# mainboard.net
KiCad netlist of a schematic drawn in EAGLE
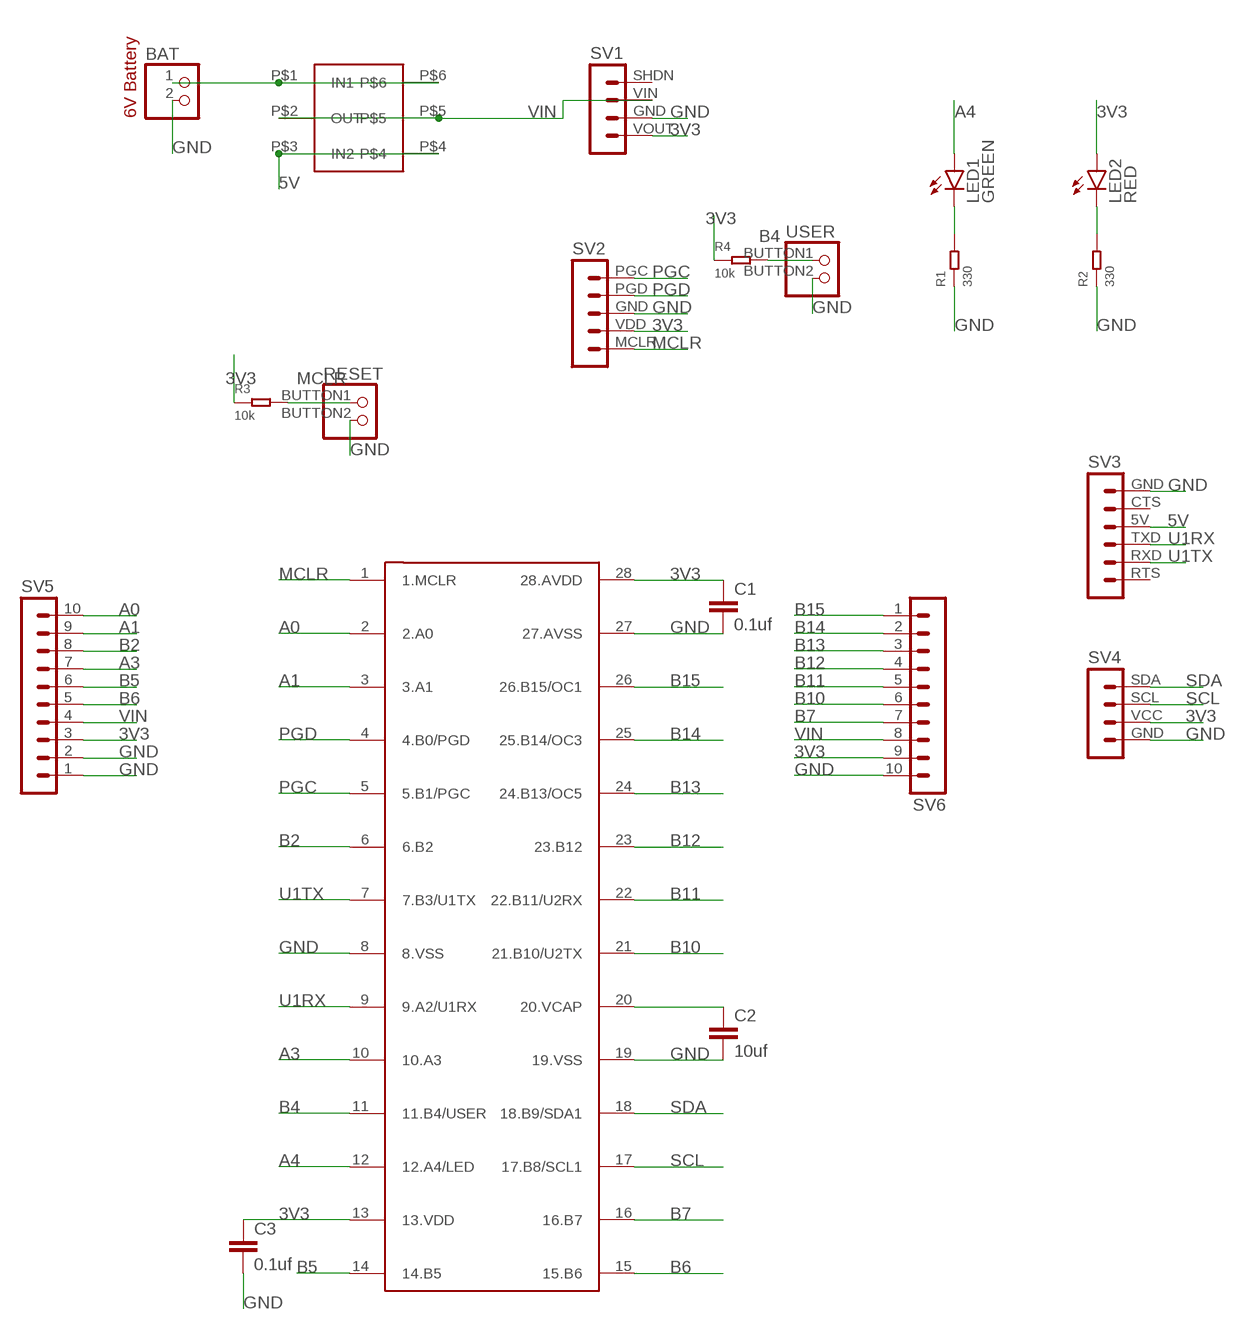
[diagram p0: schematic, sheet 1]

(export (version "E")
  (design (tool "Eeschema 10.0.6"))
  (components
    (comp (ref "BAT")
      (value "PINHD-1X2")
      (footprint "eagle-import:1X02")
      (libsource (lib "eagle-import") (part "PINHD-1X2"))
    )
    (comp (ref "C1")
      (value "0.1uf")
      (footprint "eagle-import:C2.5-3")
      (libsource (lib "eagle-import") (part "C2,5-3"))
    )
    (comp (ref "C2")
      (value "10uf")
      (footprint "eagle-import:C2.5-3")
      (libsource (lib "eagle-import") (part "C2,5-3"))
    )
    (comp (ref "C3")
      (value "0.1uf")
      (footprint "eagle-import:C2.5-3")
      (libsource (lib "eagle-import") (part "C2,5-3"))
    )
    (comp (ref "LED1")
      (value "GREEN")
      (footprint "eagle-import:LED3MM")
      (libsource (lib "eagle-import") (part "LED3MM"))
    )
    (comp (ref "LED2")
      (value "RED")
      (footprint "eagle-import:LED3MM")
      (libsource (lib "eagle-import") (part "LED3MM"))
    )
    (comp (ref "R1")
      (value "330")
      (footprint "eagle-import:PR-D2.3XL6.5MM")
      (fields (field (name "MPN") "FHCFR-1/4W-334J"))
      (libsource (lib "eagle-import") (part "DIP-RES-1/4W(PR-D2.3XL6.5MM)"))
    )
    (comp (ref "R2")
      (value "330")
      (footprint "eagle-import:PR-D2.3XL6.5MM")
      (fields (field (name "MPN") "FHCFR-1/4W-334J"))
      (libsource (lib "eagle-import") (part "DIP-RES-1/4W(PR-D2.3XL6.5MM)"))
    )
    (comp (ref "R3")
      (value "10k")
      (footprint "eagle-import:PR-D2.3XL6.5MM")
      (fields (field (name "MPN") "FHCFR-1/4W-334J"))
      (libsource (lib "eagle-import") (part "DIP-RES-1/4W(PR-D2.3XL6.5MM)"))
    )
    (comp (ref "R4")
      (value "10k")
      (footprint "eagle-import:PR-D2.3XL6.5MM")
      (fields (field (name "MPN") "FHCFR-1/4W-334J"))
      (libsource (lib "eagle-import") (part "DIP-RES-1/4W(PR-D2.3XL6.5MM)"))
    )
    (comp (ref "RESET")
      (value "PUSHBUTTON")
      (footprint "eagle-import:PUSHBUTTON")
      (libsource (lib "eagle-import") (part "PUSHBUTTON"))
    )
    (comp (ref "SV1")
      (value "POLOLU3.3POLOLU3.3")
      (footprint "eagle-import:POLOLU3.3")
      (libsource (lib "eagle-import") (part "POLOLU3.3POLOLU3.3"))
    )
    (comp (ref "SV2")
      (value "MPLAB-SNAP")
      (footprint "eagle-import:MPLAB-SNAP")
      (libsource (lib "eagle-import") (part "MPLAB-SNAP"))
    )
    (comp (ref "SV3")
      (value "CP2104FRIEND")
      (footprint "eagle-import:CP2104FRIEND")
      (libsource (lib "eagle-import") (part "CP2104FRIEND"))
    )
    (comp (ref "SV4")
      (value "SSD1306")
      (footprint "eagle-import:SSD1306")
      (libsource (lib "eagle-import") (part "SSD1306"))
    )
    (comp (ref "SV5")
      (value "MA10-1")
      (footprint "eagle-import:MA10-1")
      (libsource (lib "eagle-import") (part "MA10-1"))
    )
    (comp (ref "SV6")
      (value "MA10-1")
      (footprint "eagle-import:MA10-1")
      (libsource (lib "eagle-import") (part "MA10-1"))
    )
    (comp (ref "U$1")
      (value "SLIDE_SWITCH")
      (footprint "eagle-import:SLIDE")
      (libsource (lib "eagle-import") (part "SLIDE_SWITCH"))
    )
    (comp (ref "U$2")
      (value "PIC32MX170F256B")
      (footprint "eagle-import:DIL28-3")
      (libsource (lib "eagle-import") (part "PIC32MX170F256B"))
    )
    (comp (ref "USER")
      (value "PUSHBUTTON")
      (footprint "eagle-import:PUSHBUTTON")
      (libsource (lib "eagle-import") (part "PUSHBUTTON"))
    )
  )
  (nets
    (net (code "1") (name "/3V3") (class "Default")
      (node (ref "C1") (pin "1") (pinfunction "1_1") (pintype "passive"))
      (node (ref "C3") (pin "1") (pinfunction "1_1") (pintype "passive"))
      (node (ref "LED2") (pin "A") (pinfunction "A_A") (pintype "passive"))
      (node (ref "R3") (pin "1") (pinfunction "1_1") (pintype "passive"))
      (node (ref "R4") (pin "1") (pinfunction "1_1") (pintype "passive"))
      (node (ref "SV1") (pin "VOUT") (pinfunction "VOUT_VOUT") (pintype "passive"))
      (node (ref "SV2") (pin "VDD") (pinfunction "VDD_VDD") (pintype "passive"))
      (node (ref "SV4") (pin "VCC") (pinfunction "VCC_VCC") (pintype "passive"))
      (node (ref "SV5") (pin "3") (pinfunction "3_3") (pintype "passive"))
      (node (ref "SV6") (pin "9") (pinfunction "9_9") (pintype "passive"))
      (node (ref "U$2") (pin "13") (pinfunction "13.VDD_13") (pintype "bidirectional"))
      (node (ref "U$2") (pin "28") (pinfunction "28.AVDD_28") (pintype "bidirectional"))
    )
    (net (code "2") (name "/5V") (class "Default")
      (node (ref "SV3") (pin "5V") (pinfunction "5V_5V") (pintype "passive"))
      (node (ref "U$1") (pin "P$3") (pinfunction "IN2_P$3") (pintype "bidirectional"))
      (node (ref "U$1") (pin "P$4") (pinfunction "P$4_P$4") (pintype "bidirectional"))
    )
    (net (code "3") (name "/A0") (class "Default")
      (node (ref "SV5") (pin "10") (pinfunction "10_10") (pintype "passive"))
      (node (ref "U$2") (pin "2") (pinfunction "2.A0_2") (pintype "bidirectional"))
    )
    (net (code "4") (name "/A1") (class "Default")
      (node (ref "SV5") (pin "9") (pinfunction "9_9") (pintype "passive"))
      (node (ref "U$2") (pin "3") (pinfunction "3.A1_3") (pintype "bidirectional"))
    )
    (net (code "5") (name "/A3") (class "Default")
      (node (ref "SV5") (pin "7") (pinfunction "7_7") (pintype "passive"))
      (node (ref "U$2") (pin "10") (pinfunction "10.A3_10") (pintype "bidirectional"))
    )
    (net (code "6") (name "/A4") (class "Default")
      (node (ref "LED1") (pin "A") (pinfunction "A_A") (pintype "passive"))
      (node (ref "U$2") (pin "12") (pinfunction "12.A4/LED_12") (pintype "bidirectional"))
    )
    (net (code "7") (name "/B2") (class "Default")
      (node (ref "SV5") (pin "8") (pinfunction "8_8") (pintype "passive"))
      (node (ref "U$2") (pin "6") (pinfunction "6.B2_6") (pintype "bidirectional"))
    )
    (net (code "8") (name "/B4") (class "Default")
      (node (ref "R4") (pin "2") (pinfunction "2_2") (pintype "passive"))
      (node (ref "U$2") (pin "11") (pinfunction "11.B4/USER_11") (pintype "bidirectional"))
      (node (ref "USER") (pin "BUTTON1") (pinfunction "1_BUTTON1") (pintype "passive"))
    )
    (net (code "9") (name "/B5") (class "Default")
      (node (ref "SV5") (pin "6") (pinfunction "6_6") (pintype "passive"))
      (node (ref "U$2") (pin "14") (pinfunction "14.B5_14") (pintype "bidirectional"))
    )
    (net (code "10") (name "/B6") (class "Default")
      (node (ref "SV5") (pin "5") (pinfunction "5_5") (pintype "passive"))
      (node (ref "U$2") (pin "15") (pinfunction "15.B6_15") (pintype "bidirectional"))
    )
    (net (code "11") (name "/B7") (class "Default")
      (node (ref "SV6") (pin "7") (pinfunction "7_7") (pintype "passive"))
      (node (ref "U$2") (pin "16") (pinfunction "16.B7_16") (pintype "bidirectional"))
    )
    (net (code "12") (name "/B10") (class "Default")
      (node (ref "SV6") (pin "6") (pinfunction "6_6") (pintype "passive"))
      (node (ref "U$2") (pin "21") (pinfunction "21.B10/U2TX_21") (pintype "bidirectional"))
    )
    (net (code "13") (name "/B11") (class "Default")
      (node (ref "SV6") (pin "5") (pinfunction "5_5") (pintype "passive"))
      (node (ref "U$2") (pin "22") (pinfunction "22.B11/U2RX_22") (pintype "bidirectional"))
    )
    (net (code "14") (name "/B12") (class "Default")
      (node (ref "SV6") (pin "4") (pinfunction "4_4") (pintype "passive"))
      (node (ref "U$2") (pin "23") (pinfunction "23.B12_23") (pintype "bidirectional"))
    )
    (net (code "15") (name "/B13") (class "Default")
      (node (ref "SV6") (pin "3") (pinfunction "3_3") (pintype "passive"))
      (node (ref "U$2") (pin "24") (pinfunction "24.B13/OC5_24") (pintype "bidirectional"))
    )
    (net (code "16") (name "/B14") (class "Default")
      (node (ref "SV6") (pin "2") (pinfunction "2_2") (pintype "passive"))
      (node (ref "U$2") (pin "25") (pinfunction "25.B14/OC3_25") (pintype "bidirectional"))
    )
    (net (code "17") (name "/B15") (class "Default")
      (node (ref "SV6") (pin "1") (pinfunction "1_1") (pintype "passive"))
      (node (ref "U$2") (pin "26") (pinfunction "26.B15/OC1_26") (pintype "bidirectional"))
    )
    (net (code "18") (name "/GND") (class "Default")
      (node (ref "BAT") (pin "2") (pinfunction "2_2") (pintype "passive"))
      (node (ref "C1") (pin "2") (pinfunction "2_2") (pintype "passive"))
      (node (ref "C2") (pin "2") (pinfunction "2_2") (pintype "passive"))
      (node (ref "C3") (pin "2") (pinfunction "2_2") (pintype "passive"))
      (node (ref "R1") (pin "1") (pinfunction "1_1") (pintype "passive"))
      (node (ref "R2") (pin "1") (pinfunction "1_1") (pintype "passive"))
      (node (ref "RESET") (pin "BUTTON2") (pinfunction "2_BUTTON2") (pintype "passive"))
      (node (ref "SV1") (pin "GND") (pinfunction "GND_GND") (pintype "passive"))
      (node (ref "SV2") (pin "GND") (pinfunction "GND_GND") (pintype "passive"))
      (node (ref "SV3") (pin "GND") (pinfunction "GND_GND") (pintype "passive"))
      (node (ref "SV4") (pin "GND") (pinfunction "GND_GND") (pintype "passive"))
      (node (ref "SV5") (pin "1") (pinfunction "1_1") (pintype "passive"))
      (node (ref "SV5") (pin "2") (pinfunction "2_2") (pintype "passive"))
      (node (ref "SV6") (pin "10") (pinfunction "10_10") (pintype "passive"))
      (node (ref "U$2") (pin "19") (pinfunction "19.VSS_19") (pintype "bidirectional"))
      (node (ref "U$2") (pin "27") (pinfunction "27.AVSS_27") (pintype "bidirectional"))
      (node (ref "U$2") (pin "8") (pinfunction "8.VSS_8") (pintype "bidirectional"))
      (node (ref "USER") (pin "BUTTON2") (pinfunction "2_BUTTON2") (pintype "passive"))
    )
    (net (code "19") (name "/MCLR") (class "Default")
      (node (ref "R3") (pin "2") (pinfunction "2_2") (pintype "passive"))
      (node (ref "RESET") (pin "BUTTON1") (pinfunction "1_BUTTON1") (pintype "passive"))
      (node (ref "SV2") (pin "MCLR") (pinfunction "MCLR_MCLR") (pintype "passive"))
      (node (ref "U$2") (pin "1") (pinfunction "1.MCLR_1") (pintype "bidirectional"))
    )
    (net (code "20") (name "/PGC") (class "Default")
      (node (ref "SV2") (pin "PGC") (pinfunction "PGC_PGC") (pintype "passive"))
      (node (ref "U$2") (pin "5") (pinfunction "5.B1/PGC_5") (pintype "bidirectional"))
    )
    (net (code "21") (name "/PGD") (class "Default")
      (node (ref "SV2") (pin "PGD") (pinfunction "PGD_PGD") (pintype "passive"))
      (node (ref "U$2") (pin "4") (pinfunction "4.B0/PGD_4") (pintype "bidirectional"))
    )
    (net (code "22") (name "/SCL") (class "Default")
      (node (ref "SV4") (pin "SCL") (pinfunction "SCL_SCL") (pintype "passive"))
      (node (ref "U$2") (pin "17") (pinfunction "17.B8/SCL1_17") (pintype "bidirectional"))
    )
    (net (code "23") (name "/SDA") (class "Default")
      (node (ref "SV4") (pin "SDA") (pinfunction "SDA_SDA") (pintype "passive"))
      (node (ref "U$2") (pin "18") (pinfunction "18.B9/SDA1_18") (pintype "bidirectional"))
    )
    (net (code "24") (name "/U1RX") (class "Default")
      (node (ref "SV3") (pin "TXD") (pinfunction "TXD_TXD") (pintype "passive"))
      (node (ref "U$2") (pin "9") (pinfunction "9.A2/U1RX_9") (pintype "bidirectional"))
    )
    (net (code "25") (name "/U1TX") (class "Default")
      (node (ref "SV3") (pin "RXD") (pinfunction "RXD_RXD") (pintype "passive"))
      (node (ref "U$2") (pin "7") (pinfunction "7.B3/U1TX_7") (pintype "bidirectional"))
    )
    (net (code "26") (name "/VIN") (class "Default")
      (node (ref "SV1") (pin "VIN") (pinfunction "VIN_VIN") (pintype "passive"))
      (node (ref "SV5") (pin "4") (pinfunction "4_4") (pintype "passive"))
      (node (ref "SV6") (pin "8") (pinfunction "8_8") (pintype "passive"))
      (node (ref "U$1") (pin "P$2") (pinfunction "OUT_P$2") (pintype "bidirectional"))
      (node (ref "U$1") (pin "P$5") (pinfunction "P$5_P$5") (pintype "bidirectional"))
    )
    (net (code "27") (name "Net-(LED1-C)") (class "Default")
      (node (ref "LED1") (pin "K") (pinfunction "C_K") (pintype "passive"))
      (node (ref "R1") (pin "2") (pinfunction "2_2") (pintype "passive"))
    )
    (net (code "28") (name "Net-(LED2-C)") (class "Default")
      (node (ref "LED2") (pin "K") (pinfunction "C_K") (pintype "passive"))
      (node (ref "R2") (pin "2") (pinfunction "2_2") (pintype "passive"))
    )
    (net (code "29") (name "Net-(U$1-IN1)") (class "Default")
      (node (ref "BAT") (pin "1") (pinfunction "1_1") (pintype "passive"))
      (node (ref "U$1") (pin "P$1") (pinfunction "IN1_P$1") (pintype "bidirectional"))
      (node (ref "U$1") (pin "P$6") (pinfunction "P$6_P$6") (pintype "bidirectional"))
    )
    (net (code "30") (name "Net-(U$2-20.VCAP)") (class "Default")
      (node (ref "C2") (pin "1") (pinfunction "1_1") (pintype "passive"))
      (node (ref "U$2") (pin "20") (pinfunction "20.VCAP_20") (pintype "bidirectional"))
    )
    (net (code "31") (name "unconnected-(SV1-PadSHDN)") (class "Default")
      (node (ref "SV1") (pin "SHDN") (pinfunction "SHDN_SHDN") (pintype "passive"))
    )
    (net (code "32") (name "unconnected-(SV3-PadCTS)") (class "Default")
      (node (ref "SV3") (pin "CTS") (pinfunction "CTS_CTS") (pintype "passive"))
    )
    (net (code "33") (name "unconnected-(SV3-PadRTS)") (class "Default")
      (node (ref "SV3") (pin "RTS") (pinfunction "RTS_RTS") (pintype "passive"))
    )
  )
)
